# Nose_Poke.net
KiCad netlist of a schematic drawn in Altium Designer
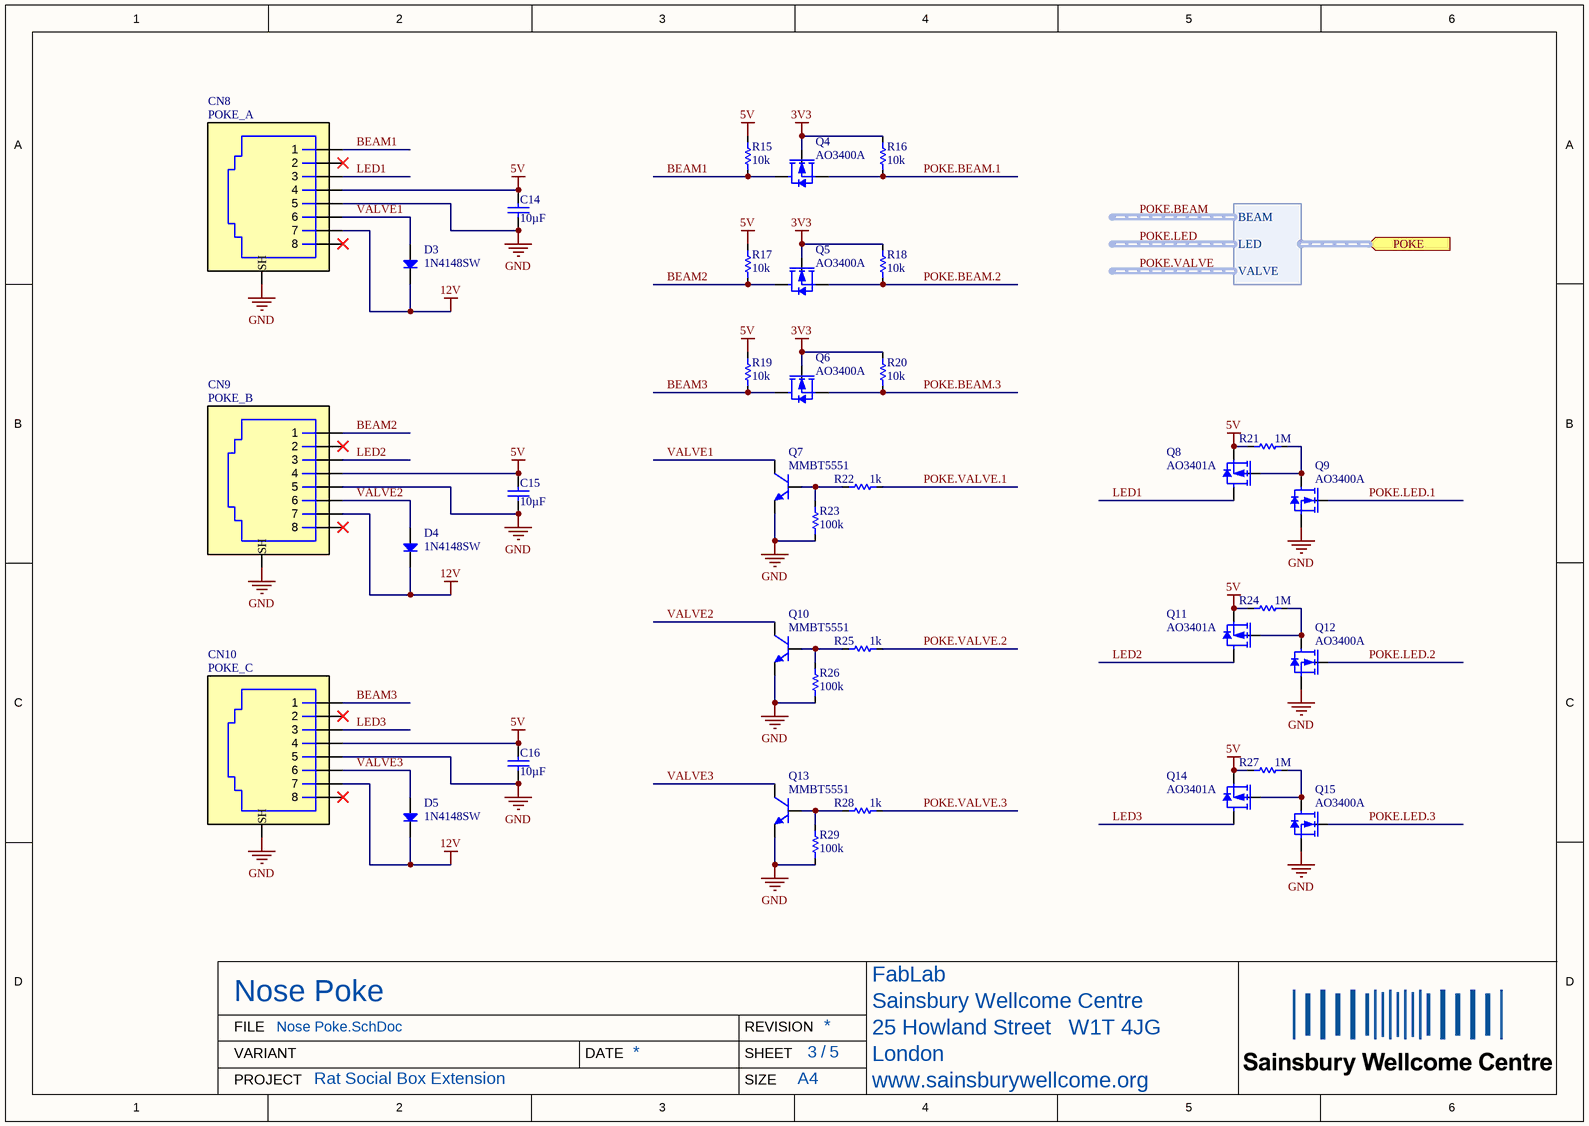
[diagram p0: Nose Poke.SchDoc]

(export (version "E")
  (design (tool "Eeschema 10.0.6"))
  (components
    (comp (ref "C14")
      (value "10µF")
      (footprint "CAP_CHIP_0603")
      (description "0603 Multilayer Ceramic Capacitors MLCC")
      (fields (field (name "PARTNUMBER") "CL10A106MA8NRNC") (field (name "TOLERANCE") "20%"))
      (libsource (lib "Sainsbury Wellcome Centre") (part "Cap"))
    )
    (comp (ref "C15")
      (value "10µF")
      (footprint "CAP_CHIP_0603")
      (description "0603 Multilayer Ceramic Capacitors MLCC")
      (fields (field (name "PARTNUMBER") "CL10A106MA8NRNC") (field (name "TOLERANCE") "20%"))
      (libsource (lib "Sainsbury Wellcome Centre") (part "Cap"))
    )
    (comp (ref "C16")
      (value "10µF")
      (footprint "CAP_CHIP_0603")
      (description "0603 Multilayer Ceramic Capacitors MLCC")
      (fields (field (name "PARTNUMBER") "CL10A106MA8NRNC") (field (name "TOLERANCE") "20%"))
      (libsource (lib "Sainsbury Wellcome Centre") (part "Cap"))
    )
    (comp (ref "CN8")
      (value "POKE_A")
      (footprint "6339160-1")
      (description "CONN MOD JACK 8P8C R/A SHIELDED")
      (fields (field (name "PARTNUMBER") "6339160-1"))
      (libsource (lib "Sainsbury Wellcome Centre") (part "RJ45"))
    )
    (comp (ref "CN9")
      (value "POKE_B")
      (footprint "6339160-1")
      (description "CONN MOD JACK 8P8C R/A SHIELDED")
      (fields (field (name "PARTNUMBER") "6339160-1"))
      (libsource (lib "Sainsbury Wellcome Centre") (part "RJ45"))
    )
    (comp (ref "CN10")
      (value "POKE_C")
      (footprint "6339160-1")
      (description "CONN MOD JACK 8P8C R/A SHIELDED")
      (fields (field (name "PARTNUMBER") "6339160-1"))
      (libsource (lib "Sainsbury Wellcome Centre") (part "RJ45"))
    )
    (comp (ref "D3")
      (value "1N4148SW")
      (footprint "SOD323")
      (description "100V Single 1.25V@150mA 4ns 150mA SOD-323 Switching Diode")
      (libsource (lib "Sainsbury Wellcome Centre") (part "Diode 2P"))
    )
    (comp (ref "D4")
      (value "1N4148SW")
      (footprint "SOD323")
      (description "100V Single 1.25V@150mA 4ns 150mA SOD-323 Switching Diode")
      (libsource (lib "Sainsbury Wellcome Centre") (part "Diode 2P"))
    )
    (comp (ref "D5")
      (value "1N4148SW")
      (footprint "SOD323")
      (description "100V Single 1.25V@150mA 4ns 150mA SOD-323 Switching Diode")
      (libsource (lib "Sainsbury Wellcome Centre") (part "Diode 2P"))
    )
    (comp (ref "Q4")
      (value "AO3400A")
      (footprint "SOT23")
      (description "30V 5.7A 26.5mΩ@10V,5.7A 1.4W 1.5V@250uA 1 NChannel SOT-23-3L MOSFETs")
      (fields (field (name "PARTNUMBER") "AO3400A"))
      (libsource (lib "Sainsbury Wellcome Centre") (part "NMOS"))
    )
    (comp (ref "Q5")
      (value "AO3400A")
      (footprint "SOT23")
      (description "30V 5.7A 26.5mΩ@10V,5.7A 1.4W 1.5V@250uA 1 NChannel SOT-23-3L MOSFETs")
      (fields (field (name "PARTNUMBER") "AO3400A"))
      (libsource (lib "Sainsbury Wellcome Centre") (part "NMOS"))
    )
    (comp (ref "Q6")
      (value "AO3400A")
      (footprint "SOT23")
      (description "30V 5.7A 26.5mΩ@10V,5.7A 1.4W 1.5V@250uA 1 NChannel SOT-23-3L MOSFETs")
      (fields (field (name "PARTNUMBER") "AO3400A"))
      (libsource (lib "Sainsbury Wellcome Centre") (part "NMOS"))
    )
    (comp (ref "Q7")
      (value "MMBT5551")
      (footprint "SOT23")
      (description "160V 300mW 200@10mA 5V 600mA NPN SOT-23 Bipolar Transistor")
      (fields (field (name "PARTNUMBER") "MMBT5551"))
      (libsource (lib "Sainsbury Wellcome Centre") (part "BJT NPN"))
    )
    (comp (ref "Q8")
      (value "AO3401A")
      (footprint "SOT23")
      (description "30V 4A 44mΩ@10V,4.3A 1.4W 1.3V@250uA 1 PChannel SOT-23-3L MOSFETs")
      (fields (field (name "PARTNUMBER") "AO3401A"))
      (libsource (lib "Sainsbury Wellcome Centre") (part "PMOS"))
    )
    (comp (ref "Q9")
      (value "AO3400A")
      (footprint "SOT23")
      (description "30V 5.7A 26.5mΩ@10V,5.7A 1.4W 1.5V@250uA 1 NChannel SOT-23-3L MOSFETs")
      (fields (field (name "PARTNUMBER") "AO3400A"))
      (libsource (lib "Sainsbury Wellcome Centre") (part "NMOS"))
    )
    (comp (ref "Q10")
      (value "MMBT5551")
      (footprint "SOT23")
      (description "160V 300mW 200@10mA 5V 600mA NPN SOT-23 Bipolar Transistor")
      (fields (field (name "PARTNUMBER") "MMBT5551"))
      (libsource (lib "Sainsbury Wellcome Centre") (part "BJT NPN"))
    )
    (comp (ref "Q11")
      (value "AO3401A")
      (footprint "SOT23")
      (description "30V 4A 44mΩ@10V,4.3A 1.4W 1.3V@250uA 1 PChannel SOT-23-3L MOSFETs")
      (fields (field (name "PARTNUMBER") "AO3401A"))
      (libsource (lib "Sainsbury Wellcome Centre") (part "PMOS"))
    )
    (comp (ref "Q12")
      (value "AO3400A")
      (footprint "SOT23")
      (description "30V 5.7A 26.5mΩ@10V,5.7A 1.4W 1.5V@250uA 1 NChannel SOT-23-3L MOSFETs")
      (fields (field (name "PARTNUMBER") "AO3400A"))
      (libsource (lib "Sainsbury Wellcome Centre") (part "NMOS"))
    )
    (comp (ref "Q13")
      (value "MMBT5551")
      (footprint "SOT23")
      (description "160V 300mW 200@10mA 5V 600mA NPN SOT-23 Bipolar Transistor")
      (fields (field (name "PARTNUMBER") "MMBT5551"))
      (libsource (lib "Sainsbury Wellcome Centre") (part "BJT NPN"))
    )
    (comp (ref "Q14")
      (value "AO3401A")
      (footprint "SOT23")
      (description "30V 4A 44mΩ@10V,4.3A 1.4W 1.3V@250uA 1 PChannel SOT-23-3L MOSFETs")
      (fields (field (name "PARTNUMBER") "AO3401A"))
      (libsource (lib "Sainsbury Wellcome Centre") (part "PMOS"))
    )
    (comp (ref "Q15")
      (value "AO3400A")
      (footprint "SOT23")
      (description "30V 5.7A 26.5mΩ@10V,5.7A 1.4W 1.5V@250uA 1 NChannel SOT-23-3L MOSFETs")
      (fields (field (name "PARTNUMBER") "AO3400A"))
      (libsource (lib "Sainsbury Wellcome Centre") (part "NMOS"))
    )
    (comp (ref "R15")
      (value "10k")
      (footprint "RES_CHIP_0603")
      (description "100mW Thick Film Resistors 75V ±100ppm/℃ ±1% 0603 Chip Resistor")
      (fields (field (name "PARTNUMBER") "0603WAF1002T5E") (field (name "TOLERANCE") "1%"))
      (libsource (lib "Sainsbury Wellcome Centre") (part "Res"))
    )
    (comp (ref "R16")
      (value "10k")
      (footprint "RES_CHIP_0603")
      (description "100mW Thick Film Resistors 75V ±100ppm/℃ ±1% 0603 Chip Resistor")
      (fields (field (name "PARTNUMBER") "0603WAF1002T5E") (field (name "TOLERANCE") "1%"))
      (libsource (lib "Sainsbury Wellcome Centre") (part "Res"))
    )
    (comp (ref "R17")
      (value "10k")
      (footprint "RES_CHIP_0603")
      (description "100mW Thick Film Resistors 75V ±100ppm/℃ ±1% 0603 Chip Resistor")
      (fields (field (name "PARTNUMBER") "0603WAF1002T5E") (field (name "TOLERANCE") "1%"))
      (libsource (lib "Sainsbury Wellcome Centre") (part "Res"))
    )
    (comp (ref "R18")
      (value "10k")
      (footprint "RES_CHIP_0603")
      (description "100mW Thick Film Resistors 75V ±100ppm/℃ ±1% 0603 Chip Resistor")
      (fields (field (name "PARTNUMBER") "0603WAF1002T5E") (field (name "TOLERANCE") "1%"))
      (libsource (lib "Sainsbury Wellcome Centre") (part "Res"))
    )
    (comp (ref "R19")
      (value "10k")
      (footprint "RES_CHIP_0603")
      (description "100mW Thick Film Resistors 75V ±100ppm/℃ ±1% 0603 Chip Resistor")
      (fields (field (name "PARTNUMBER") "0603WAF1002T5E") (field (name "TOLERANCE") "1%"))
      (libsource (lib "Sainsbury Wellcome Centre") (part "Res"))
    )
    (comp (ref "R20")
      (value "10k")
      (footprint "RES_CHIP_0603")
      (description "100mW Thick Film Resistors 75V ±100ppm/℃ ±1% 0603 Chip Resistor")
      (fields (field (name "PARTNUMBER") "0603WAF1002T5E") (field (name "TOLERANCE") "1%"))
      (libsource (lib "Sainsbury Wellcome Centre") (part "Res"))
    )
    (comp (ref "R21")
      (value "1M")
      (footprint "RES_CHIP_0603")
      (description "100mW Thick Film Resistors 75V ±100ppm/℃ ±1% 0603 Chip Resistor")
      (fields (field (name "PARTNUMBER") "0603WAF1004T5E") (field (name "TOLERANCE") "1%"))
      (libsource (lib "Sainsbury Wellcome Centre") (part "Res"))
    )
    (comp (ref "R22")
      (value "1k")
      (footprint "RES_CHIP_0603")
      (description "100mW Thick Film Resistors 75V ±100ppm/℃ ±1% 0603 Chip Resistor")
      (fields (field (name "PARTNUMBER") "0603WAF1001T5E") (field (name "TOLERANCE") "1%"))
      (libsource (lib "Sainsbury Wellcome Centre") (part "Res"))
    )
    (comp (ref "R23")
      (value "100k")
      (footprint "RES_CHIP_0603")
      (description "100mW Thick Film Resistors 75V ±100ppm/℃ ±1% 0603 Chip Resistor")
      (fields (field (name "PARTNUMBER") "0603WAF1003T5E") (field (name "TOLERANCE") "1%"))
      (libsource (lib "Sainsbury Wellcome Centre") (part "Res"))
    )
    (comp (ref "R24")
      (value "1M")
      (footprint "RES_CHIP_0603")
      (description "100mW Thick Film Resistors 75V ±100ppm/℃ ±1% 0603 Chip Resistor")
      (fields (field (name "PARTNUMBER") "0603WAF1004T5E") (field (name "TOLERANCE") "1%"))
      (libsource (lib "Sainsbury Wellcome Centre") (part "Res"))
    )
    (comp (ref "R25")
      (value "1k")
      (footprint "RES_CHIP_0603")
      (description "100mW Thick Film Resistors 75V ±100ppm/℃ ±1% 0603 Chip Resistor")
      (fields (field (name "PARTNUMBER") "0603WAF1001T5E") (field (name "TOLERANCE") "1%"))
      (libsource (lib "Sainsbury Wellcome Centre") (part "Res"))
    )
    (comp (ref "R26")
      (value "100k")
      (footprint "RES_CHIP_0603")
      (description "100mW Thick Film Resistors 75V ±100ppm/℃ ±1% 0603 Chip Resistor")
      (fields (field (name "PARTNUMBER") "0603WAF1003T5E") (field (name "TOLERANCE") "1%"))
      (libsource (lib "Sainsbury Wellcome Centre") (part "Res"))
    )
    (comp (ref "R27")
      (value "1M")
      (footprint "RES_CHIP_0603")
      (description "100mW Thick Film Resistors 75V ±100ppm/℃ ±1% 0603 Chip Resistor")
      (fields (field (name "PARTNUMBER") "0603WAF1004T5E") (field (name "TOLERANCE") "1%"))
      (libsource (lib "Sainsbury Wellcome Centre") (part "Res"))
    )
    (comp (ref "R28")
      (value "1k")
      (footprint "RES_CHIP_0603")
      (description "100mW Thick Film Resistors 75V ±100ppm/℃ ±1% 0603 Chip Resistor")
      (fields (field (name "PARTNUMBER") "0603WAF1001T5E") (field (name "TOLERANCE") "1%"))
      (libsource (lib "Sainsbury Wellcome Centre") (part "Res"))
    )
    (comp (ref "R29")
      (value "100k")
      (footprint "RES_CHIP_0603")
      (description "100mW Thick Film Resistors 75V ±100ppm/℃ ±1% 0603 Chip Resistor")
      (fields (field (name "PARTNUMBER") "0603WAF1003T5E") (field (name "TOLERANCE") "1%"))
      (libsource (lib "Sainsbury Wellcome Centre") (part "Res"))
    )
  )
  (nets
    (net (code "5") (name "/BEAM1") (class "Default")
      (node (ref "CN8") (pin "1") (pinfunction "1_1") (pintype "passive"))
      (node (ref "Q4") (pin "3") (pinfunction "D_3") (pintype "passive"))
      (node (ref "R15") (pin "1") (pinfunction "1_1") (pintype "passive"))
    )
    (net (code "6") (name "/BEAM2") (class "Default")
      (node (ref "CN9") (pin "1") (pinfunction "1_1") (pintype "passive"))
      (node (ref "Q5") (pin "3") (pinfunction "D_3") (pintype "passive"))
      (node (ref "R17") (pin "1") (pinfunction "1_1") (pintype "passive"))
    )
    (net (code "7") (name "/BEAM3") (class "Default")
      (node (ref "CN10") (pin "1") (pinfunction "1_1") (pintype "passive"))
      (node (ref "Q6") (pin "3") (pinfunction "D_3") (pintype "passive"))
      (node (ref "R19") (pin "1") (pinfunction "1_1") (pintype "passive"))
    )
    (net (code "8") (name "/LED1") (class "Default")
      (node (ref "CN8") (pin "3") (pinfunction "3_3") (pintype "passive"))
      (node (ref "Q8") (pin "3") (pinfunction "D_3") (pintype "passive"))
    )
    (net (code "9") (name "/LED2") (class "Default")
      (node (ref "CN9") (pin "3") (pinfunction "3_3") (pintype "passive"))
      (node (ref "Q11") (pin "3") (pinfunction "D_3") (pintype "passive"))
    )
    (net (code "10") (name "/LED3") (class "Default")
      (node (ref "CN10") (pin "3") (pinfunction "3_3") (pintype "passive"))
      (node (ref "Q14") (pin "3") (pinfunction "D_3") (pintype "passive"))
    )
    (net (code "11") (name "/POKE.BEAM.1") (class "Default")
      (node (ref "Q4") (pin "2") (pinfunction "S_2") (pintype "passive"))
      (node (ref "R16") (pin "1") (pinfunction "1_1") (pintype "passive"))
    )
    (net (code "12") (name "/POKE.BEAM.2") (class "Default")
      (node (ref "Q5") (pin "2") (pinfunction "S_2") (pintype "passive"))
      (node (ref "R18") (pin "1") (pinfunction "1_1") (pintype "passive"))
    )
    (net (code "13") (name "/POKE.BEAM.3") (class "Default")
      (node (ref "Q6") (pin "2") (pinfunction "S_2") (pintype "passive"))
      (node (ref "R20") (pin "1") (pinfunction "1_1") (pintype "passive"))
    )
    (net (code "14") (name "/POKE.LED.1") (class "Default")
      (node (ref "Q9") (pin "1") (pinfunction "G_1") (pintype "passive"))
    )
    (net (code "15") (name "/POKE.LED.2") (class "Default")
      (node (ref "Q12") (pin "1") (pinfunction "G_1") (pintype "passive"))
    )
    (net (code "16") (name "/POKE.LED.3") (class "Default")
      (node (ref "Q15") (pin "1") (pinfunction "G_1") (pintype "passive"))
    )
    (net (code "17") (name "/POKE.VALVE.1") (class "Default")
      (node (ref "R22") (pin "2") (pinfunction "2_2") (pintype "passive"))
    )
    (net (code "18") (name "/POKE.VALVE.2") (class "Default")
      (node (ref "R25") (pin "2") (pinfunction "2_2") (pintype "passive"))
    )
    (net (code "19") (name "/POKE.VALVE.3") (class "Default")
      (node (ref "R28") (pin "2") (pinfunction "2_2") (pintype "passive"))
    )
    (net (code "20") (name "/VALVE1") (class "Default")
      (node (ref "CN8") (pin "6") (pinfunction "6_6") (pintype "passive"))
      (node (ref "D3") (pin "2") (pinfunction "A_2") (pintype "passive"))
      (node (ref "Q7") (pin "3") (pinfunction "C_3") (pintype "passive"))
    )
    (net (code "21") (name "/VALVE2") (class "Default")
      (node (ref "CN9") (pin "6") (pinfunction "6_6") (pintype "passive"))
      (node (ref "D4") (pin "2") (pinfunction "A_2") (pintype "passive"))
      (node (ref "Q10") (pin "3") (pinfunction "C_3") (pintype "passive"))
    )
    (net (code "22") (name "/VALVE3") (class "Default")
      (node (ref "CN10") (pin "6") (pinfunction "6_6") (pintype "passive"))
      (node (ref "D5") (pin "2") (pinfunction "A_2") (pintype "passive"))
      (node (ref "Q13") (pin "3") (pinfunction "C_3") (pintype "passive"))
    )
    (net (code "27") (name "3V3") (class "Default")
      (node (ref "Q4") (pin "1") (pinfunction "G_1") (pintype "passive"))
      (node (ref "Q5") (pin "1") (pinfunction "G_1") (pintype "passive"))
      (node (ref "Q6") (pin "1") (pinfunction "G_1") (pintype "passive"))
      (node (ref "R16") (pin "2") (pinfunction "2_2") (pintype "passive"))
      (node (ref "R18") (pin "2") (pinfunction "2_2") (pintype "passive"))
      (node (ref "R20") (pin "2") (pinfunction "2_2") (pintype "passive"))
    )
    (net (code "28") (name "5V") (class "Default")
      (node (ref "C14") (pin "2") (pinfunction "2_2") (pintype "passive"))
      (node (ref "C15") (pin "2") (pinfunction "2_2") (pintype "passive"))
      (node (ref "C16") (pin "2") (pinfunction "2_2") (pintype "passive"))
      (node (ref "CN10") (pin "4") (pinfunction "4_4") (pintype "passive"))
      (node (ref "CN8") (pin "4") (pinfunction "4_4") (pintype "passive"))
      (node (ref "CN9") (pin "4") (pinfunction "4_4") (pintype "passive"))
      (node (ref "Q11") (pin "2") (pinfunction "S_2") (pintype "passive"))
      (node (ref "Q14") (pin "2") (pinfunction "S_2") (pintype "passive"))
      (node (ref "Q8") (pin "2") (pinfunction "S_2") (pintype "passive"))
      (node (ref "R15") (pin "2") (pinfunction "2_2") (pintype "passive"))
      (node (ref "R17") (pin "2") (pinfunction "2_2") (pintype "passive"))
      (node (ref "R19") (pin "2") (pinfunction "2_2") (pintype "passive"))
      (node (ref "R21") (pin "2") (pinfunction "2_2") (pintype "passive"))
      (node (ref "R24") (pin "2") (pinfunction "2_2") (pintype "passive"))
      (node (ref "R27") (pin "2") (pinfunction "2_2") (pintype "passive"))
    )
    (net (code "29") (name "12V") (class "Default")
      (node (ref "CN10") (pin "7") (pinfunction "7_7") (pintype "passive"))
      (node (ref "CN8") (pin "7") (pinfunction "7_7") (pintype "passive"))
      (node (ref "CN9") (pin "7") (pinfunction "7_7") (pintype "passive"))
      (node (ref "D3") (pin "1") (pinfunction "K_1") (pintype "passive"))
      (node (ref "D4") (pin "1") (pinfunction "K_1") (pintype "passive"))
      (node (ref "D5") (pin "1") (pinfunction "K_1") (pintype "passive"))
    )
    (net (code "30") (name "GND") (class "Default")
      (node (ref "C14") (pin "1") (pinfunction "1_1") (pintype "passive"))
      (node (ref "C15") (pin "1") (pinfunction "1_1") (pintype "passive"))
      (node (ref "C16") (pin "1") (pinfunction "1_1") (pintype "passive"))
      (node (ref "CN10") (pin "0") (pinfunction "SH_0") (pintype "passive"))
      (node (ref "CN10") (pin "5") (pinfunction "5_5") (pintype "passive"))
      (node (ref "CN8") (pin "0") (pinfunction "SH_0") (pintype "passive"))
      (node (ref "CN8") (pin "5") (pinfunction "5_5") (pintype "passive"))
      (node (ref "CN9") (pin "0") (pinfunction "SH_0") (pintype "passive"))
      (node (ref "CN9") (pin "5") (pinfunction "5_5") (pintype "passive"))
      (node (ref "Q10") (pin "2") (pinfunction "E_2") (pintype "passive"))
      (node (ref "Q12") (pin "2") (pinfunction "S_2") (pintype "passive"))
      (node (ref "Q13") (pin "2") (pinfunction "E_2") (pintype "passive"))
      (node (ref "Q15") (pin "2") (pinfunction "S_2") (pintype "passive"))
      (node (ref "Q7") (pin "2") (pinfunction "E_2") (pintype "passive"))
      (node (ref "Q9") (pin "2") (pinfunction "S_2") (pintype "passive"))
      (node (ref "R23") (pin "1") (pinfunction "1_1") (pintype "passive"))
      (node (ref "R26") (pin "1") (pinfunction "1_1") (pintype "passive"))
      (node (ref "R29") (pin "1") (pinfunction "1_1") (pintype "passive"))
    )
    (net (code "31") (name "Net-(Q7-B)") (class "Default")
      (node (ref "Q7") (pin "1") (pinfunction "B_1") (pintype "passive"))
      (node (ref "R22") (pin "1") (pinfunction "1_1") (pintype "passive"))
      (node (ref "R23") (pin "2") (pinfunction "2_2") (pintype "passive"))
    )
    (net (code "32") (name "Net-(Q8-G)") (class "Default")
      (node (ref "Q8") (pin "1") (pinfunction "G_1") (pintype "passive"))
      (node (ref "Q9") (pin "3") (pinfunction "D_3") (pintype "passive"))
      (node (ref "R21") (pin "1") (pinfunction "1_1") (pintype "passive"))
    )
    (net (code "33") (name "Net-(Q10-B)") (class "Default")
      (node (ref "Q10") (pin "1") (pinfunction "B_1") (pintype "passive"))
      (node (ref "R25") (pin "1") (pinfunction "1_1") (pintype "passive"))
      (node (ref "R26") (pin "2") (pinfunction "2_2") (pintype "passive"))
    )
    (net (code "34") (name "Net-(Q11-G)") (class "Default")
      (node (ref "Q11") (pin "1") (pinfunction "G_1") (pintype "passive"))
      (node (ref "Q12") (pin "3") (pinfunction "D_3") (pintype "passive"))
      (node (ref "R24") (pin "1") (pinfunction "1_1") (pintype "passive"))
    )
    (net (code "35") (name "Net-(Q13-B)") (class "Default")
      (node (ref "Q13") (pin "1") (pinfunction "B_1") (pintype "passive"))
      (node (ref "R28") (pin "1") (pinfunction "1_1") (pintype "passive"))
      (node (ref "R29") (pin "2") (pinfunction "2_2") (pintype "passive"))
    )
    (net (code "36") (name "Net-(Q14-G)") (class "Default")
      (node (ref "Q14") (pin "1") (pinfunction "G_1") (pintype "passive"))
      (node (ref "Q15") (pin "3") (pinfunction "D_3") (pintype "passive"))
      (node (ref "R27") (pin "1") (pinfunction "1_1") (pintype "passive"))
    )
    (net (code "37") (name "unconnected-(CN8-Pad2)") (class "Default")
      (node (ref "CN8") (pin "2") (pinfunction "2_2") (pintype "passive+no_connect"))
    )
    (net (code "38") (name "unconnected-(CN8-Pad8)") (class "Default")
      (node (ref "CN8") (pin "8") (pinfunction "8_8") (pintype "passive+no_connect"))
    )
    (net (code "39") (name "unconnected-(CN9-Pad2)") (class "Default")
      (node (ref "CN9") (pin "2") (pinfunction "2_2") (pintype "passive+no_connect"))
    )
    (net (code "40") (name "unconnected-(CN9-Pad8)") (class "Default")
      (node (ref "CN9") (pin "8") (pinfunction "8_8") (pintype "passive+no_connect"))
    )
    (net (code "41") (name "unconnected-(CN10-Pad2)") (class "Default")
      (node (ref "CN10") (pin "2") (pinfunction "2_2") (pintype "passive+no_connect"))
    )
    (net (code "42") (name "unconnected-(CN10-Pad8)") (class "Default")
      (node (ref "CN10") (pin "8") (pinfunction "8_8") (pintype "passive+no_connect"))
    )
  )
)
